# main_sch.net
KiCad netlist of a schematic drawn in Altium Designer
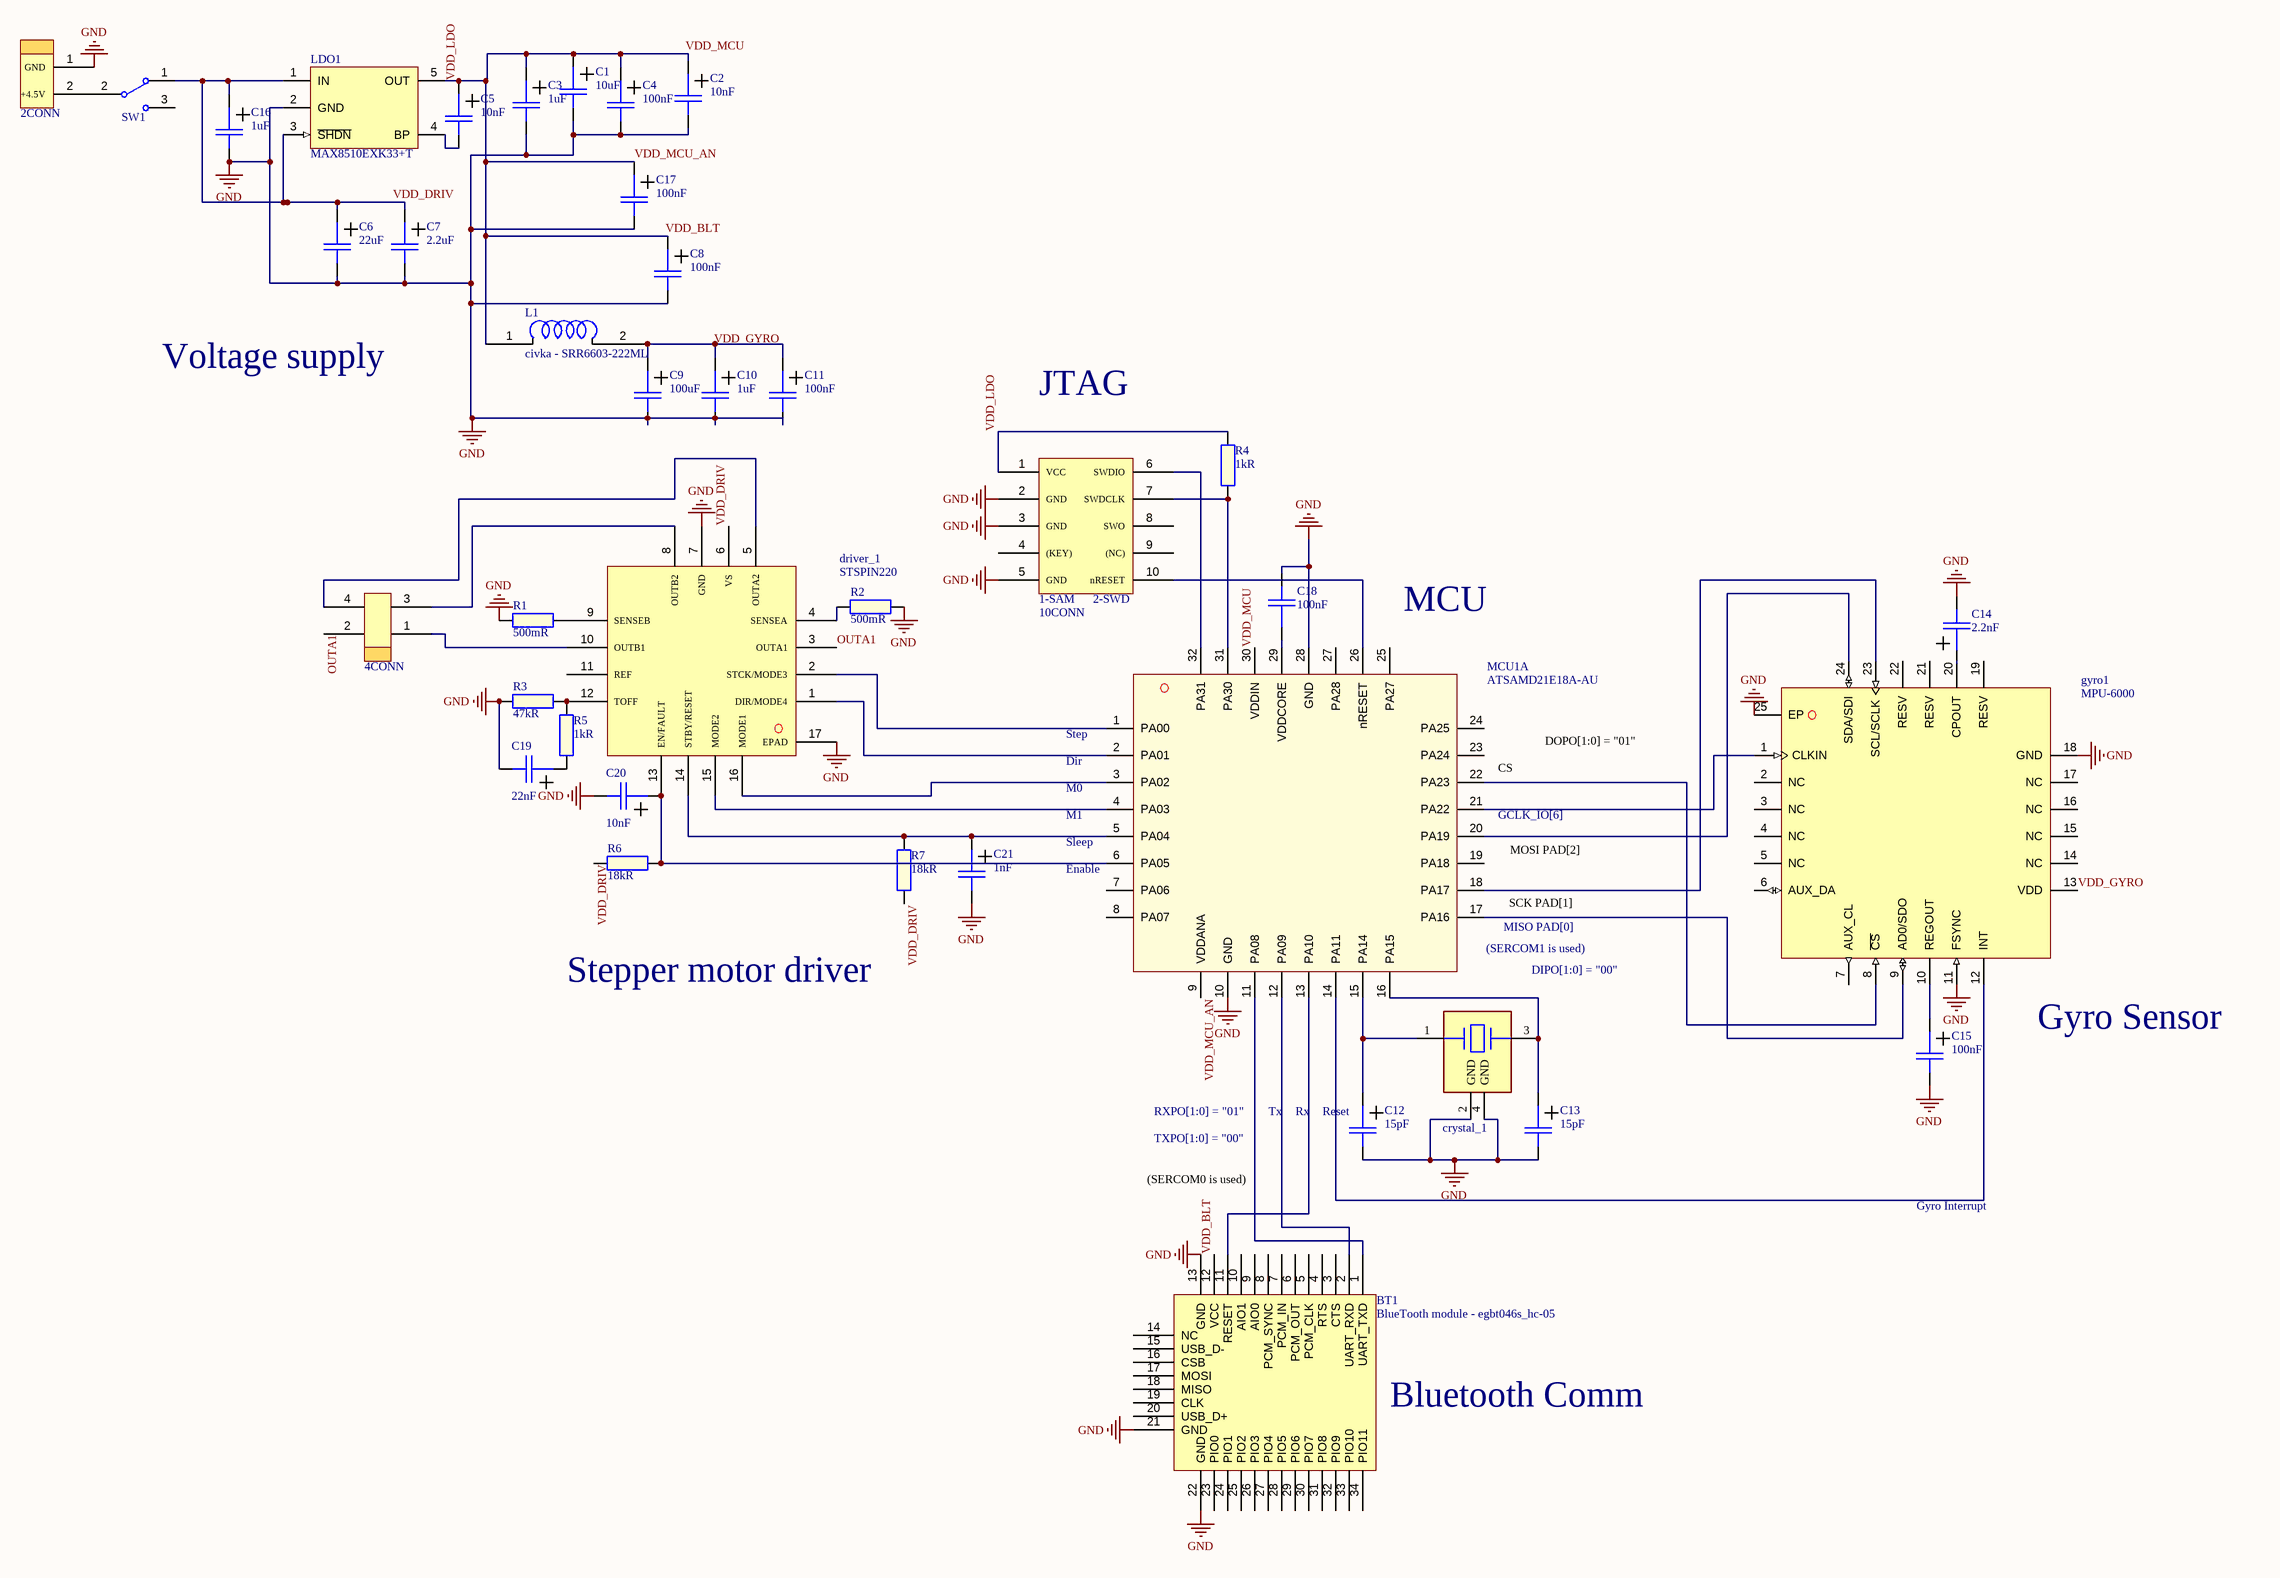
[diagram p0: main_sch.SchDoc]

(export (version "E")
  (design (tool "Eeschema 10.0.6"))
  (components
    (comp (ref "2CONN")
      (value "39-30-1020")
      (footprint "39-30-1020")
      (description "Connector Wire to Board Header 2 Position 4.2mm Solder Right Angle Thru-Hole Bag")
      (fields (field (name "MANUFACTURER") "Molex"))
      (libsource (lib "int_lib_pendulum") (part "39-30-1020"))
    )
    (comp (ref "4CONN")
      (value "39-30-1040")
      (footprint "39-30-1040")
      (description "Connector Wire to Board Header 4 Position 4.2mm Solder Right Angle Thru-Hole Tray")
      (fields (field (name "MANUFACTURER") "Molex"))
      (libsource (lib "int_lib_pendulum") (part "39-30-1040"))
    )
    (comp (ref "10CONN")
      (value "konektor - GPEA214-0502A005C1BA")
      (footprint "konektor - GPEA214-0502A005C1BA")
      (description "Connector, Header, 10POS, 2ROW, 1.27MM")
      (fields
        (field (name "MANUFACTURER") "Greenconn")
        (field (name "MANUFACTURER PART NUMBER") "GPEA214-0502A005C1BA")
      )
      (libsource (lib "int_lib_pendulum") (part "konektor - GPEA214-0502A005C1BA"))
    )
    (comp (ref "BT1")
      (value "BlueTooth module - egbt046s_hc-05")
      (footprint "BT_EGBT-046S")
      (libsource (lib "int_lib_pendulum") (part "BlueTooth module - egbt046s_hc-05"))
    )
    (comp (ref "C1")
      (value "10uF")
      (footprint "0805 (2x1.2)")
      (libsource (lib "int_lib_pendulum") (part "C0805 (2x1.2)"))
    )
    (comp (ref "C2")
      (value "10nF")
      (footprint "0805 (2x1.2)")
      (libsource (lib "int_lib_pendulum") (part "C0805 (2x1.2)"))
    )
    (comp (ref "C3")
      (value "1uF")
      (footprint "0805 (2x1.2)")
      (libsource (lib "int_lib_pendulum") (part "C0805 (2x1.2)"))
    )
    (comp (ref "C4")
      (value "100nF")
      (footprint "0805 (2x1.2)")
      (libsource (lib "int_lib_pendulum") (part "C0805 (2x1.2)"))
    )
    (comp (ref "C5")
      (value "10nF")
      (footprint "0805 (2x1.2)")
      (libsource (lib "int_lib_pendulum") (part "C0805 (2x1.2)"))
    )
    (comp (ref "C6")
      (value "22uF")
      (footprint "0805 (2x1.2)")
      (libsource (lib "int_lib_pendulum") (part "C0805 (2x1.2)"))
    )
    (comp (ref "C7")
      (value "2.2uF")
      (footprint "0805 (2x1.2)")
      (libsource (lib "int_lib_pendulum") (part "C0805 (2x1.2)"))
    )
    (comp (ref "C8")
      (value "100nF")
      (footprint "0805 (2x1.2)")
      (libsource (lib "int_lib_pendulum") (part "C0805 (2x1.2)"))
    )
    (comp (ref "C9")
      (value "100uF")
      (footprint "0805 (2x1.2)")
      (libsource (lib "int_lib_pendulum") (part "C0805 (2x1.2)"))
    )
    (comp (ref "C10")
      (value "1uF")
      (footprint "0805 (2x1.2)")
      (libsource (lib "int_lib_pendulum") (part "C0805 (2x1.2)"))
    )
    (comp (ref "C11")
      (value "100nF")
      (footprint "0805 (2x1.2)")
      (libsource (lib "int_lib_pendulum") (part "C0805 (2x1.2)"))
    )
    (comp (ref "C12")
      (value "15pF")
      (footprint "0805 (2x1.2)")
      (libsource (lib "int_lib_pendulum") (part "C0805 (2x1.2)"))
    )
    (comp (ref "C13")
      (value "15pF")
      (footprint "0805 (2x1.2)")
      (libsource (lib "int_lib_pendulum") (part "C0805 (2x1.2)"))
    )
    (comp (ref "C14")
      (value "2.2nF")
      (footprint "0805 (2x1.2)")
      (libsource (lib "int_lib_pendulum") (part "C0805 (2x1.2)"))
    )
    (comp (ref "C15")
      (value "100nF")
      (footprint "0805 (2x1.2)")
      (libsource (lib "int_lib_pendulum") (part "C0805 (2x1.2)"))
    )
    (comp (ref "C16")
      (value "1uF")
      (footprint "0805 (2x1.2)")
      (libsource (lib "int_lib_pendulum") (part "C0805 (2x1.2)"))
    )
    (comp (ref "C17")
      (value "100nF")
      (footprint "0805 (2x1.2)")
      (libsource (lib "int_lib_pendulum") (part "C0805 (2x1.2)"))
    )
    (comp (ref "C18")
      (value "100nF")
      (footprint "0805 (2x1.2)")
      (libsource (lib "") (part "C0805 (2x1.2)_1"))
    )
    (comp (ref "C19")
      (value "22nF")
      (footprint "0805 (2x1.2)")
      (libsource (lib "int_lib_pendulum") (part "C0805 (2x1.2)"))
    )
    (comp (ref "C20")
      (value "10nF")
      (footprint "0805 (2x1.2)")
      (libsource (lib "int_lib_pendulum") (part "C0805 (2x1.2)"))
    )
    (comp (ref "C21")
      (value "1nF")
      (footprint "0805 (2x1.2)")
      (libsource (lib "int_lib_pendulum") (part "C0805 (2x1.2)"))
    )
    (comp (ref "crystal_1")
      (value "ABM8G-25.000MHz-B4Y-T")
      (footprint "crystal 3.2x2.5")
      (description "CRYSTAL 25.0000MHZ 10PF SMD")
      (fields (field (name "TOLERANCE") "30ppm"))
      (libsource (lib "int_lib_pendulum") (part "crystal 3.2x2.5"))
    )
    (comp (ref "driver_1")
      (value "STSPIN220")
      (footprint "driver - STSPIN220")
      (description "STSPIN220 Series 10 V Quad Surface Mount Stepper Motor Driver - VFQFPN-16")
      (fields (field (name "MANUFACTURER") "STMicroelectronics"))
      (libsource (lib "int_lib_pendulum") (part "driver - STSPIN220"))
    )
    (comp (ref "gyro1")
      (value "MPU-6000")
      (footprint "gyro - MPU 6000")
      (fields (field (name "MANUFACTURER") "InvenSense"))
      (libsource (lib "int_lib_pendulum") (part "gyro - MPU 6000"))
    )
    (comp (ref "L1")
      (value "civka - SRR6603-222ML")
      (footprint "L_SRR6603-222ML")
      (description "Inductor Power Shielded Wirewound 2200uH 20% 100KHz 50Q-Factor Ferrite 0.1A 8.5Ohm DCR T/R")
      (fields
        (field (name "MANUFACTURER") "Bourns")
        (field (name "MANUFACTURER PART NUMBER") "SRR6603-222ML")
      )
      (libsource (lib "int_lib_pendulum") (part "civka - SRR6603-222ML"))
    )
    (comp (ref "LDO1")
      (value "MAX8510EXK33+T")
      (footprint "LDO - MAX8510EXK33+T (SC70)")
      (libsource (lib "int_lib_pendulum") (part "LDO - MAX8510EXK33+T"))
    )
    (comp (ref "MCU1")
      (value "ATSAMD21E18A-AU")
      (footprint "MCU- ATSAMD21E18A-AU")
      (description "Low-Power, 32-bit Cortex-M0+ MCU with advanced Analog and PWM")
      (libsource (lib "int_lib_pendulum") (part "MCU - ATSAMD21E18A-AU"))
    )
    (comp (ref "R1")
      (value "500mR")
      (footprint "0805 (2x1.2)")
      (description "Resistor 470R, 1206, 1%")
      (libsource (lib "") (part "R0805_2"))
    )
    (comp (ref "R2")
      (value "500mR")
      (footprint "0805 (2x1.2)")
      (description "Resistor 470R, 1206, 1%")
      (libsource (lib "int_lib_pendulum") (part "R0805"))
    )
    (comp (ref "R3")
      (value "47kR")
      (footprint "0805 (2x1.2)")
      (description "Resistor 470R, 1206, 1%")
      (libsource (lib "int_lib_pendulum") (part "R0805"))
    )
    (comp (ref "R4")
      (value "1kR")
      (footprint "0805 (2x1.2)")
      (description "Resistor 470R, 1206, 1%")
      (libsource (lib "") (part "R0805_1"))
    )
    (comp (ref "R5")
      (value "1kR")
      (footprint "0805 (2x1.2)")
      (description "Resistor 470R, 1206, 1%")
      (libsource (lib "") (part "R0805_3"))
    )
    (comp (ref "R6")
      (value "18kR")
      (footprint "0805 (2x1.2)")
      (description "Resistor 470R, 1206, 1%")
      (libsource (lib "int_lib_pendulum") (part "R0805"))
    )
    (comp (ref "R7")
      (value "18kR")
      (footprint "0805 (2x1.2)")
      (description "Resistor 470R, 1206, 1%")
      (libsource (lib "") (part "R0805_1"))
    )
    (comp (ref "SW1")
      (value "EG1218")
      (footprint "vypinac - EG1218")
      (description "Slide Switch, 500 V, -20 to 70 degC, 3-Pin THD, RoHS")
      (libsource (lib "int_lib_pendulum") (part "vypinac - EG1218"))
    )
  )
  (nets
    (net (code "1") (name "/OUTA1") (class "Default")
      (node (ref "4CONN") (pin "2") (pinfunction "2_2") (pintype "passive"))
      (node (ref "driver_1") (pin "3") (pinfunction "OUTA1_3") (pintype "passive"))
    )
    (net (code "2") (name "/VDD_BLT") (class "Default")
      (node (ref "10CONN") (pin "1") (pinfunction "VCC_1") (pintype "passive"))
      (node (ref "BT1") (pin "12") (pinfunction "VCC_12") (pintype "passive"))
      (node (ref "C1") (pin "1") (pinfunction "1_1") (pintype "passive"))
      (node (ref "C17") (pin "1") (pinfunction "1_1") (pintype "passive"))
      (node (ref "C2") (pin "1") (pinfunction "1_1") (pintype "passive"))
      (node (ref "C3") (pin "1") (pinfunction "1_1") (pintype "passive"))
      (node (ref "C4") (pin "1") (pinfunction "1_1") (pintype "passive"))
      (node (ref "C5") (pin "1") (pinfunction "1_1") (pintype "passive"))
      (node (ref "C8") (pin "1") (pinfunction "1_1") (pintype "passive"))
      (node (ref "L1") (pin "1") (pinfunction "1_1") (pintype "passive"))
      (node (ref "LDO1") (pin "5") (pinfunction "OUT_5") (pintype "power_in"))
      (node (ref "MCU1") (pin "30") (pinfunction "VDDIN_30") (pintype "passive"))
      (node (ref "MCU1") (pin "9") (pinfunction "VDDANA_9") (pintype "passive"))
      (node (ref "R4") (pin "2") (pinfunction "2_2") (pintype "passive"))
    )
    (net (code "3") (name "/VDD_DRIV") (class "Default")
      (node (ref "C16") (pin "1") (pinfunction "1_1") (pintype "passive"))
      (node (ref "C6") (pin "1") (pinfunction "1_1") (pintype "passive"))
      (node (ref "C7") (pin "1") (pinfunction "1_1") (pintype "passive"))
      (node (ref "LDO1") (pin "1") (pinfunction "IN_1") (pintype "power_in"))
      (node (ref "LDO1") (pin "3") (pinfunction "~{SHDN}_3") (pintype "input"))
      (node (ref "R6") (pin "2") (pinfunction "2_2") (pintype "passive"))
      (node (ref "R7") (pin "1") (pinfunction "1_1") (pintype "passive"))
      (node (ref "SW1") (pin "1") (pinfunction "1_1") (pintype "passive"))
      (node (ref "driver_1") (pin "6") (pinfunction "VS_6") (pintype "passive"))
    )
    (net (code "4") (name "/VDD_GYRO") (class "Default")
      (node (ref "gyro1") (pin "13") (pinfunction "VDD_13") (pintype "power_in"))
    )
    (net (code "5") (name "GND") (class "Default")
      (node (ref "10CONN") (pin "2") (pinfunction "GND_2") (pintype "passive"))
      (node (ref "10CONN") (pin "3") (pinfunction "GND_3") (pintype "passive"))
      (node (ref "10CONN") (pin "5") (pinfunction "GND_5") (pintype "passive"))
      (node (ref "2CONN") (pin "1") (pinfunction "GND_1") (pintype "passive"))
      (node (ref "BT1") (pin "13") (pinfunction "GND_13") (pintype "passive"))
      (node (ref "BT1") (pin "21") (pinfunction "GND_21") (pintype "passive"))
      (node (ref "BT1") (pin "22") (pinfunction "GND_22") (pintype "passive"))
      (node (ref "C1") (pin "2") (pinfunction "2_2") (pintype "passive"))
      (node (ref "C10") (pin "2") (pinfunction "2_2") (pintype "passive"))
      (node (ref "C11") (pin "2") (pinfunction "2_2") (pintype "passive"))
      (node (ref "C12") (pin "2") (pinfunction "2_2") (pintype "passive"))
      (node (ref "C13") (pin "2") (pinfunction "2_2") (pintype "passive"))
      (node (ref "C14") (pin "2") (pinfunction "2_2") (pintype "passive"))
      (node (ref "C15") (pin "2") (pinfunction "2_2") (pintype "passive"))
      (node (ref "C16") (pin "2") (pinfunction "2_2") (pintype "passive"))
      (node (ref "C17") (pin "2") (pinfunction "2_2") (pintype "passive"))
      (node (ref "C18") (pin "2") (pinfunction "2_2") (pintype "passive"))
      (node (ref "C19") (pin "2") (pinfunction "2_2") (pintype "passive"))
      (node (ref "C2") (pin "2") (pinfunction "2_2") (pintype "passive"))
      (node (ref "C20") (pin "2") (pinfunction "2_2") (pintype "passive"))
      (node (ref "C21") (pin "2") (pinfunction "2_2") (pintype "passive"))
      (node (ref "C3") (pin "2") (pinfunction "2_2") (pintype "passive"))
      (node (ref "C4") (pin "2") (pinfunction "2_2") (pintype "passive"))
      (node (ref "C6") (pin "2") (pinfunction "2_2") (pintype "passive"))
      (node (ref "C7") (pin "2") (pinfunction "2_2") (pintype "passive"))
      (node (ref "C8") (pin "2") (pinfunction "2_2") (pintype "passive"))
      (node (ref "C9") (pin "2") (pinfunction "2_2") (pintype "passive"))
      (node (ref "LDO1") (pin "2") (pinfunction "GND_2") (pintype "power_in"))
      (node (ref "MCU1") (pin "10") (pinfunction "GND_10") (pintype "passive"))
      (node (ref "MCU1") (pin "28") (pinfunction "GND_28") (pintype "passive"))
      (node (ref "R1") (pin "1") (pinfunction "1_1") (pintype "passive"))
      (node (ref "R2") (pin "1") (pinfunction "1_1") (pintype "passive"))
      (node (ref "R3") (pin "2") (pinfunction "2_2") (pintype "passive"))
      (node (ref "crystal_1") (pin "2") (pinfunction "GND_2") (pintype "power_in"))
      (node (ref "crystal_1") (pin "4") (pinfunction "GND_4") (pintype "power_in"))
      (node (ref "driver_1") (pin "17") (pinfunction "EPAD_17") (pintype "passive"))
      (node (ref "driver_1") (pin "7") (pinfunction "GND_7") (pintype "passive"))
      (node (ref "gyro1") (pin "11") (pinfunction "FSYNC_11") (pintype "input"))
      (node (ref "gyro1") (pin "18") (pinfunction "GND_18") (pintype "power_in"))
      (node (ref "gyro1") (pin "25") (pinfunction "EP_25") (pintype "passive"))
    )
    (net (code "6") (name "Net-(2CONN-+4.5V)") (class "Default")
      (node (ref "2CONN") (pin "2") (pinfunction "+4.5V_2") (pintype "passive"))
      (node (ref "SW1") (pin "2") (pinfunction "COM_2") (pintype "passive"))
    )
    (net (code "7") (name "Net-(10CONN-SWDCLK)") (class "Default")
      (node (ref "10CONN") (pin "7") (pinfunction "SWDCLK_7") (pintype "passive"))
      (node (ref "MCU1") (pin "31") (pinfunction "PA30_31") (pintype "passive"))
      (node (ref "R4") (pin "1") (pinfunction "1_1") (pintype "passive"))
    )
    (net (code "8") (name "Net-(10CONN-SWDIO)") (class "Default")
      (node (ref "10CONN") (pin "6") (pinfunction "SWDIO_6") (pintype "passive"))
      (node (ref "MCU1") (pin "32") (pinfunction "PA31_32") (pintype "passive"))
    )
    (net (code "9") (name "Net-(10CONN-nRESET)") (class "Default")
      (node (ref "10CONN") (pin "10") (pinfunction "nRESET_10") (pintype "passive"))
      (node (ref "MCU1") (pin "26") (pinfunction "nRESET_26") (pintype "passive"))
    )
    (net (code "10") (name "Net-(BT1-RESET)") (class "Default")
      (node (ref "BT1") (pin "11") (pinfunction "RESET_11") (pintype "passive"))
      (node (ref "MCU1") (pin "13") (pinfunction "PA10_13") (pintype "passive"))
    )
    (net (code "11") (name "Net-(BT1-UART_RXD)") (class "Default")
      (node (ref "BT1") (pin "2") (pinfunction "UART_RXD_2") (pintype "passive"))
      (node (ref "MCU1") (pin "12") (pinfunction "PA09_12") (pintype "passive"))
    )
    (net (code "12") (name "Net-(BT1-UART_TXD)") (class "Default")
      (node (ref "BT1") (pin "1") (pinfunction "UART_TXD_1") (pintype "passive"))
      (node (ref "MCU1") (pin "11") (pinfunction "PA08_11") (pintype "passive"))
    )
    (net (code "13") (name "Net-(C10-Pad1)") (class "Default")
      (node (ref "C10") (pin "1") (pinfunction "1_1") (pintype "passive"))
      (node (ref "C11") (pin "1") (pinfunction "1_1") (pintype "passive"))
      (node (ref "C9") (pin "1") (pinfunction "1_1") (pintype "passive"))
      (node (ref "L1") (pin "2") (pinfunction "2_2") (pintype "passive"))
    )
    (net (code "14") (name "Net-(C19-Pad1)") (class "Default")
      (node (ref "C19") (pin "1") (pinfunction "1_1") (pintype "passive"))
      (node (ref "R5") (pin "2") (pinfunction "2_2") (pintype "passive"))
    )
    (net (code "15") (name "Net-(LDO1-BP)") (class "Default")
      (node (ref "C5") (pin "2") (pinfunction "2_2") (pintype "passive"))
      (node (ref "LDO1") (pin "4") (pinfunction "BP_4") (pintype "passive"))
    )
    (net (code "16") (name "Net-(MCU1A-PA00)") (class "Default")
      (node (ref "MCU1") (pin "1") (pinfunction "PA00_1") (pintype "passive"))
      (node (ref "driver_1") (pin "2") (pinfunction "STCK/MODE3_2") (pintype "passive"))
    )
    (net (code "17") (name "Net-(MCU1A-PA01)") (class "Default")
      (node (ref "MCU1") (pin "2") (pinfunction "PA01_2") (pintype "passive"))
      (node (ref "driver_1") (pin "1") (pinfunction "DIR/MODE4_1") (pintype "passive"))
    )
    (net (code "18") (name "Net-(MCU1A-PA02)") (class "Default")
      (node (ref "MCU1") (pin "3") (pinfunction "PA02_3") (pintype "passive"))
      (node (ref "driver_1") (pin "16") (pinfunction "MODE1_16") (pintype "passive"))
    )
    (net (code "19") (name "Net-(MCU1A-PA03)") (class "Default")
      (node (ref "MCU1") (pin "4") (pinfunction "PA03_4") (pintype "passive"))
      (node (ref "driver_1") (pin "15") (pinfunction "MODE2_15") (pintype "passive"))
    )
    (net (code "20") (name "Net-(MCU1A-PA04)") (class "Default")
      (node (ref "C21") (pin "1") (pinfunction "1_1") (pintype "passive"))
      (node (ref "MCU1") (pin "5") (pinfunction "PA04_5") (pintype "passive"))
      (node (ref "R7") (pin "2") (pinfunction "2_2") (pintype "passive"))
      (node (ref "driver_1") (pin "14") (pinfunction "STBY/RESET_14") (pintype "passive"))
    )
    (net (code "21") (name "Net-(MCU1A-PA05)") (class "Default")
      (node (ref "C20") (pin "1") (pinfunction "1_1") (pintype "passive"))
      (node (ref "MCU1") (pin "6") (pinfunction "PA05_6") (pintype "passive"))
      (node (ref "R6") (pin "1") (pinfunction "1_1") (pintype "passive"))
      (node (ref "driver_1") (pin "13") (pinfunction "EN/FAULT_13") (pintype "passive"))
    )
    (net (code "22") (name "Net-(MCU1A-PA11)") (class "Default")
      (node (ref "MCU1") (pin "14") (pinfunction "PA11_14") (pintype "passive"))
      (node (ref "gyro1") (pin "12") (pinfunction "INT_12") (pintype "open_collector"))
    )
    (net (code "23") (name "Net-(MCU1A-PA14)") (class "Default")
      (node (ref "C12") (pin "1") (pinfunction "1_1") (pintype "passive"))
      (node (ref "MCU1") (pin "15") (pinfunction "PA14_15") (pintype "passive"))
      (node (ref "crystal_1") (pin "1") (pinfunction "1_1") (pintype "passive"))
    )
    (net (code "24") (name "Net-(MCU1A-PA15)") (class "Default")
      (node (ref "C13") (pin "1") (pinfunction "1_1") (pintype "passive"))
      (node (ref "MCU1") (pin "16") (pinfunction "PA15_16") (pintype "passive"))
      (node (ref "crystal_1") (pin "3") (pinfunction "3_3") (pintype "passive"))
    )
    (net (code "25") (name "Net-(MCU1A-PA16)") (class "Default")
      (node (ref "MCU1") (pin "17") (pinfunction "PA16_17") (pintype "passive"))
      (node (ref "gyro1") (pin "9") (pinfunction "AD0/SDO_9") (pintype "bidirectional"))
    )
    (net (code "26") (name "Net-(MCU1A-PA17)") (class "Default")
      (node (ref "MCU1") (pin "18") (pinfunction "PA17_18") (pintype "passive"))
      (node (ref "gyro1") (pin "23") (pinfunction "SCL/SCLK_23") (pintype "input"))
    )
    (net (code "27") (name "Net-(MCU1A-PA19)") (class "Default")
      (node (ref "MCU1") (pin "20") (pinfunction "PA19_20") (pintype "passive"))
      (node (ref "gyro1") (pin "24") (pinfunction "SDA/SDI_24") (pintype "bidirectional"))
    )
    (net (code "28") (name "Net-(MCU1A-PA22)") (class "Default")
      (node (ref "MCU1") (pin "21") (pinfunction "PA22_21") (pintype "passive"))
      (node (ref "gyro1") (pin "1") (pinfunction "CLKIN_1") (pintype "input"))
    )
    (net (code "29") (name "Net-(MCU1A-PA23)") (class "Default")
      (node (ref "MCU1") (pin "22") (pinfunction "PA23_22") (pintype "passive"))
      (node (ref "gyro1") (pin "8") (pinfunction "~{CS}_8") (pintype "input"))
    )
    (net (code "30") (name "Net-(MCU1A-VDDCORE)") (class "Default")
      (node (ref "C18") (pin "1") (pinfunction "1_1") (pintype "passive"))
      (node (ref "MCU1") (pin "29") (pinfunction "VDDCORE_29") (pintype "passive"))
    )
    (net (code "31") (name "Net-(driver_1-OUTA2)") (class "Default")
      (node (ref "4CONN") (pin "4") (pinfunction "4_4") (pintype "passive"))
      (node (ref "driver_1") (pin "5") (pinfunction "OUTA2_5") (pintype "passive"))
    )
    (net (code "32") (name "Net-(driver_1-OUTB1)") (class "Default")
      (node (ref "4CONN") (pin "1") (pinfunction "1_1") (pintype "passive"))
      (node (ref "driver_1") (pin "10") (pinfunction "OUTB1_10") (pintype "passive"))
    )
    (net (code "33") (name "Net-(driver_1-OUTB2)") (class "Default")
      (node (ref "4CONN") (pin "3") (pinfunction "3_3") (pintype "passive"))
      (node (ref "driver_1") (pin "8") (pinfunction "OUTB2_8") (pintype "passive"))
    )
    (net (code "34") (name "Net-(driver_1-SENSEA)") (class "Default")
      (node (ref "R2") (pin "2") (pinfunction "2_2") (pintype "passive"))
      (node (ref "driver_1") (pin "4") (pinfunction "SENSEA_4") (pintype "passive"))
    )
    (net (code "35") (name "Net-(driver_1-SENSEB)") (class "Default")
      (node (ref "R1") (pin "2") (pinfunction "2_2") (pintype "passive"))
      (node (ref "driver_1") (pin "9") (pinfunction "SENSEB_9") (pintype "passive"))
    )
    (net (code "36") (name "Net-(driver_1-TOFF)") (class "Default")
      (node (ref "R3") (pin "1") (pinfunction "1_1") (pintype "passive"))
      (node (ref "R5") (pin "1") (pinfunction "1_1") (pintype "passive"))
      (node (ref "driver_1") (pin "12") (pinfunction "TOFF_12") (pintype "passive"))
    )
    (net (code "37") (name "Net-(gyro1-CPOUT)") (class "Default")
      (node (ref "C14") (pin "1") (pinfunction "1_1") (pintype "passive"))
      (node (ref "gyro1") (pin "20") (pinfunction "CPOUT_20") (pintype "passive"))
    )
    (net (code "38") (name "Net-(gyro1-REGOUT)") (class "Default")
      (node (ref "C15") (pin "1") (pinfunction "1_1") (pintype "passive"))
      (node (ref "gyro1") (pin "10") (pinfunction "REGOUT_10") (pintype "passive"))
    )
    (net (code "39") (name "unconnected-(10CONN-(KEY)-Pad4)") (class "Default")
      (node (ref "10CONN") (pin "4") (pinfunction "(KEY)_4") (pintype "passive"))
    )
    (net (code "40") (name "unconnected-(10CONN-(NC)-Pad9)") (class "Default")
      (node (ref "10CONN") (pin "9") (pinfunction "(NC)_9") (pintype "passive"))
    )
    (net (code "41") (name "unconnected-(10CONN-SWO-Pad8)") (class "Default")
      (node (ref "10CONN") (pin "8") (pinfunction "SWO_8") (pintype "passive"))
    )
    (net (code "42") (name "unconnected-(BT1-AIO0-Pad9)") (class "Default")
      (node (ref "BT1") (pin "9") (pinfunction "AIO0_9") (pintype "passive"))
    )
    (net (code "43") (name "unconnected-(BT1-AIO1-Pad10)") (class "Default")
      (node (ref "BT1") (pin "10") (pinfunction "AIO1_10") (pintype "passive"))
    )
    (net (code "44") (name "unconnected-(BT1-CLK-Pad19)") (class "Default")
      (node (ref "BT1") (pin "19") (pinfunction "CLK_19") (pintype "passive"))
    )
    (net (code "45") (name "unconnected-(BT1-CSB-Pad16)") (class "Default")
      (node (ref "BT1") (pin "16") (pinfunction "CSB_16") (pintype "passive"))
    )
    (net (code "46") (name "unconnected-(BT1-CTS-Pad3)") (class "Default")
      (node (ref "BT1") (pin "3") (pinfunction "CTS_3") (pintype "passive"))
    )
    (net (code "47") (name "unconnected-(BT1-MISO-Pad18)") (class "Default")
      (node (ref "BT1") (pin "18") (pinfunction "MISO_18") (pintype "passive"))
    )
    (net (code "48") (name "unconnected-(BT1-MOSI-Pad17)") (class "Default")
      (node (ref "BT1") (pin "17") (pinfunction "MOSI_17") (pintype "passive"))
    )
    (net (code "49") (name "unconnected-(BT1-NC-Pad14)") (class "Default")
      (node (ref "BT1") (pin "14") (pinfunction "NC_14") (pintype "passive"))
    )
    (net (code "50") (name "unconnected-(BT1-PCM_CLK-Pad5)") (class "Default")
      (node (ref "BT1") (pin "5") (pinfunction "PCM_CLK_5") (pintype "passive"))
    )
    (net (code "51") (name "unconnected-(BT1-PCM_IN-Pad7)") (class "Default")
      (node (ref "BT1") (pin "7") (pinfunction "PCM_IN_7") (pintype "passive"))
    )
    (net (code "52") (name "unconnected-(BT1-PCM_OUT-Pad6)") (class "Default")
      (node (ref "BT1") (pin "6") (pinfunction "PCM_OUT_6") (pintype "passive"))
    )
    (net (code "53") (name "unconnected-(BT1-PCM_SYNC-Pad8)") (class "Default")
      (node (ref "BT1") (pin "8") (pinfunction "PCM_SYNC_8") (pintype "passive"))
    )
    (net (code "54") (name "unconnected-(BT1-PIO0-Pad23)") (class "Default")
      (node (ref "BT1") (pin "23") (pinfunction "PIO0_23") (pintype "passive"))
    )
    (net (code "55") (name "unconnected-(BT1-PIO1-Pad24)") (class "Default")
      (node (ref "BT1") (pin "24") (pinfunction "PIO1_24") (pintype "passive"))
    )
    (net (code "56") (name "unconnected-(BT1-PIO2-Pad25)") (class "Default")
      (node (ref "BT1") (pin "25") (pinfunction "PIO2_25") (pintype "passive"))
    )
    (net (code "57") (name "unconnected-(BT1-PIO3-Pad26)") (class "Default")
      (node (ref "BT1") (pin "26") (pinfunction "PIO3_26") (pintype "passive"))
    )
    (net (code "58") (name "unconnected-(BT1-PIO4-Pad27)") (class "Default")
      (node (ref "BT1") (pin "27") (pinfunction "PIO4_27") (pintype "passive"))
    )
    (net (code "59") (name "unconnected-(BT1-PIO5-Pad28)") (class "Default")
      (node (ref "BT1") (pin "28") (pinfunction "PIO5_28") (pintype "passive"))
    )
    (net (code "60") (name "unconnected-(BT1-PIO6-Pad29)") (class "Default")
      (node (ref "BT1") (pin "29") (pinfunction "PIO6_29") (pintype "passive"))
    )
    (net (code "61") (name "unconnected-(BT1-PIO7-Pad30)") (class "Default")
      (node (ref "BT1") (pin "30") (pinfunction "PIO7_30") (pintype "passive"))
    )
    (net (code "62") (name "unconnected-(BT1-PIO8-Pad31)") (class "Default")
      (node (ref "BT1") (pin "31") (pinfunction "PIO8_31") (pintype "passive"))
    )
    (net (code "63") (name "unconnected-(BT1-PIO9-Pad32)") (class "Default")
      (node (ref "BT1") (pin "32") (pinfunction "PIO9_32") (pintype "passive"))
    )
    (net (code "64") (name "unconnected-(BT1-PIO10-Pad33)") (class "Default")
      (node (ref "BT1") (pin "33") (pinfunction "PIO10_33") (pintype "passive"))
    )
    (net (code "65") (name "unconnected-(BT1-PIO11-Pad34)") (class "Default")
      (node (ref "BT1") (pin "34") (pinfunction "PIO11_34") (pintype "passive"))
    )
    (net (code "66") (name "unconnected-(BT1-RTS-Pad4)") (class "Default")
      (node (ref "BT1") (pin "4") (pinfunction "RTS_4") (pintype "passive"))
    )
    (net (code "67") (name "unconnected-(BT1-USB_D+-Pad20)") (class "Default")
      (node (ref "BT1") (pin "20") (pinfunction "USB_D+_20") (pintype "passive"))
    )
    (net (code "68") (name "unconnected-(BT1-USB_D--Pad15)") (class "Default")
      (node (ref "BT1") (pin "15") (pinfunction "USB_D-_15") (pintype "passive"))
    )
    (net (code "69") (name "unconnected-(MCU1A-PA06-Pad7)") (class "Default")
      (node (ref "MCU1") (pin "7") (pinfunction "PA06_7") (pintype "passive"))
    )
    (net (code "70") (name "unconnected-(MCU1A-PA07-Pad8)") (class "Default")
      (node (ref "MCU1") (pin "8") (pinfunction "PA07_8") (pintype "passive"))
    )
    (net (code "71") (name "unconnected-(MCU1A-PA18-Pad19)") (class "Default")
      (node (ref "MCU1") (pin "19") (pinfunction "PA18_19") (pintype "passive"))
    )
    (net (code "72") (name "unconnected-(MCU1A-PA24-Pad23)") (class "Default")
      (node (ref "MCU1") (pin "23") (pinfunction "PA24_23") (pintype "passive"))
    )
    (net (code "73") (name "unconnected-(MCU1A-PA25-Pad24)") (class "Default")
      (node (ref "MCU1") (pin "24") (pinfunction "PA25_24") (pintype "passive"))
    )
    (net (code "74") (name "unconnected-(MCU1A-PA27-Pad25)") (class "Default")
      (node (ref "MCU1") (pin "25") (pinfunction "PA27_25") (pintype "passive"))
    )
    (net (code "75") (name "unconnected-(MCU1A-PA28-Pad27)") (class "Default")
      (node (ref "MCU1") (pin "27") (pinfunction "PA28_27") (pintype "passive"))
    )
    (net (code "76") (name "unconnected-(SW1-Pad3)") (class "Default")
      (node (ref "SW1") (pin "3") (pinfunction "3_3") (pintype "passive"))
    )
    (net (code "77") (name "unconnected-(driver_1-REF-Pad11)") (class "Default")
      (node (ref "driver_1") (pin "11") (pinfunction "REF_11") (pintype "passive"))
    )
    (net (code "78") (name "unconnected-(gyro1-AUX_CL-Pad7)") (class "Default")
      (node (ref "gyro1") (pin "7") (pinfunction "AUX_CL_7") (pintype "output"))
    )
    (net (code "79") (name "unconnected-(gyro1-AUX_DA-Pad6)") (class "Default")
      (node (ref "gyro1") (pin "6") (pinfunction "AUX_DA_6") (pintype "bidirectional"))
    )
    (net (code "80") (name "unconnected-(gyro1-NC-Pad2)") (class "Default")
      (node (ref "gyro1") (pin "2") (pinfunction "NC_2") (pintype "passive"))
    )
    (net (code "81") (name "unconnected-(gyro1-NC-Pad3)") (class "Default")
      (node (ref "gyro1") (pin "3") (pinfunction "NC_3") (pintype "passive"))
    )
    (net (code "82") (name "unconnected-(gyro1-NC-Pad4)") (class "Default")
      (node (ref "gyro1") (pin "4") (pinfunction "NC_4") (pintype "passive"))
    )
    (net (code "83") (name "unconnected-(gyro1-NC-Pad5)") (class "Default")
      (node (ref "gyro1") (pin "5") (pinfunction "NC_5") (pintype "passive"))
    )
    (net (code "84") (name "unconnected-(gyro1-NC-Pad14)") (class "Default")
      (node (ref "gyro1") (pin "14") (pinfunction "NC_14") (pintype "passive"))
    )
    (net (code "85") (name "unconnected-(gyro1-NC-Pad15)") (class "Default")
      (node (ref "gyro1") (pin "15") (pinfunction "NC_15") (pintype "passive"))
    )
    (net (code "86") (name "unconnected-(gyro1-NC-Pad16)") (class "Default")
      (node (ref "gyro1") (pin "16") (pinfunction "NC_16") (pintype "passive"))
    )
    (net (code "87") (name "unconnected-(gyro1-NC-Pad17)") (class "Default")
      (node (ref "gyro1") (pin "17") (pinfunction "NC_17") (pintype "passive"))
    )
    (net (code "88") (name "unconnected-(gyro1-RESV-Pad19)") (class "Default")
      (node (ref "gyro1") (pin "19") (pinfunction "RESV_19") (pintype "passive"))
    )
    (net (code "89") (name "unconnected-(gyro1-RESV-Pad21)") (class "Default")
      (node (ref "gyro1") (pin "21") (pinfunction "RESV_21") (pintype "passive"))
    )
    (net (code "90") (name "unconnected-(gyro1-RESV-Pad22)") (class "Default")
      (node (ref "gyro1") (pin "22") (pinfunction "RESV_22") (pintype "passive"))
    )
  )
)
